# User_Interface.net
KiCad netlist of a schematic drawn in Altium Designer
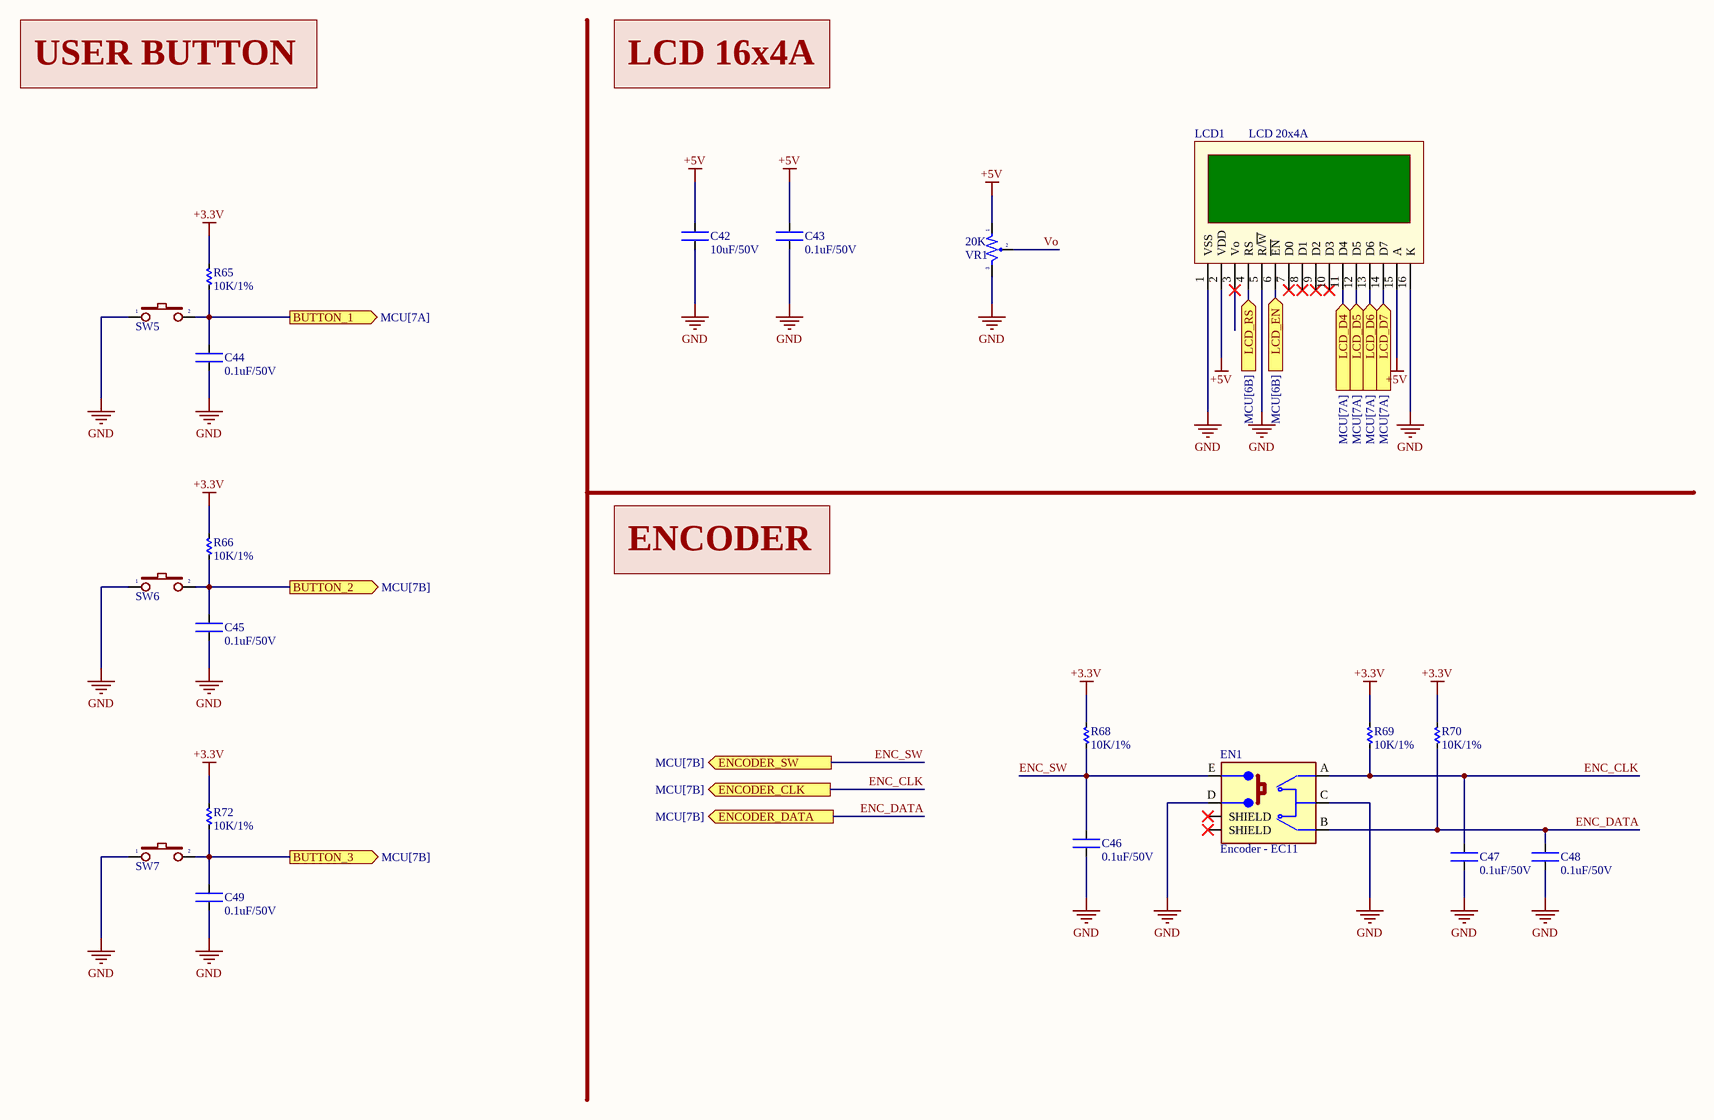
[diagram p0: User_Interface.SchDoc]

(export (version "E")
  (design (tool "Eeschema 10.0.6"))
  (components
    (comp (ref "C42")
      (value "10uF/50V")
      (footprint "CAP - 0603")
      (description "CAPACITOR SMD - KEMET")
      (libsource (lib "NewLibrary") (part "CAPACITOR"))
    )
    (comp (ref "C43")
      (value "0.1uF/50V")
      (footprint "CAP - 0603")
      (description "CAPACITOR SMD - KEMET")
      (libsource (lib "NewLibrary") (part "CAPACITOR"))
    )
    (comp (ref "C44")
      (value "0.1uF/50V")
      (footprint "CAP - 0603")
      (description "CAPACITOR SMD - KEMET")
      (libsource (lib "NewLibrary") (part "CAPACITOR"))
    )
    (comp (ref "C45")
      (value "0.1uF/50V")
      (footprint "CAP - 0603")
      (description "CAPACITOR SMD - KEMET")
      (libsource (lib "NewLibrary") (part "CAPACITOR"))
    )
    (comp (ref "C46")
      (value "0.1uF/50V")
      (footprint "CAP - 0603")
      (description "CAPACITOR SMD - KEMET")
      (libsource (lib "NewLibrary") (part "CAPACITOR"))
    )
    (comp (ref "C47")
      (value "0.1uF/50V")
      (footprint "CAP - 0603")
      (description "CAPACITOR SMD - KEMET")
      (libsource (lib "NewLibrary") (part "CAPACITOR"))
    )
    (comp (ref "C48")
      (value "0.1uF/50V")
      (footprint "CAP - 0603")
      (description "CAPACITOR SMD - KEMET")
      (libsource (lib "NewLibrary") (part "CAPACITOR"))
    )
    (comp (ref "C49")
      (value "0.1uF/50V")
      (footprint "CAP - 0603")
      (description "CAPACITOR SMD - KEMET")
      (libsource (lib "NewLibrary") (part "CAPACITOR"))
    )
    (comp (ref "EN1")
      (value "Encoder - EC11")
      (footprint "Encoder - EC11")
      (description "Bourns PEC11R-4015F-S0024")
      (libsource (lib "NewLibrary") (part "Encoder - EC11"))
    )
    (comp (ref "LCD1")
      (value "LCD 20x4A")
      (footprint "LCD-20x4A-4-Holes")
      (description "LCD 2004")
      (libsource (lib "NewLibrary") (part "LCD 20x4A"))
    )
    (comp (ref "R65")
      (value "10K/1%")
      (footprint "RES - 0603")
      (description "Resistor SMD - YAGEO")
      (libsource (lib "NewLibrary") (part "RESISTOR"))
    )
    (comp (ref "R66")
      (value "10K/1%")
      (footprint "RES - 0603")
      (description "Resistor SMD - YAGEO")
      (libsource (lib "NewLibrary") (part "RESISTOR"))
    )
    (comp (ref "R68")
      (value "10K/1%")
      (footprint "RES - 0603")
      (description "Resistor SMD - YAGEO")
      (libsource (lib "NewLibrary") (part "RESISTOR"))
    )
    (comp (ref "R69")
      (value "10K/1%")
      (footprint "RES - 0603")
      (description "Resistor SMD - YAGEO")
      (libsource (lib "NewLibrary") (part "RESISTOR"))
    )
    (comp (ref "R70")
      (value "10K/1%")
      (footprint "RES - 0603")
      (description "Resistor SMD - YAGEO")
      (libsource (lib "NewLibrary") (part "RESISTOR"))
    )
    (comp (ref "R72")
      (value "10K/1%")
      (footprint "RES - 0603")
      (description "Resistor SMD - YAGEO")
      (libsource (lib "NewLibrary") (part "RESISTOR"))
    )
    (comp (ref "SW5")
      (value "Button 4 Pins")
      (footprint "SW-SMD-6x6mm")
      (description "DIP Button 4 Pins")
      (libsource (lib "NewLibrary") (part "Button 4 Pins"))
    )
    (comp (ref "SW6")
      (value "Button 4 Pins")
      (footprint "SW-SMD-6x6mm")
      (description "DIP Button 4 Pins")
      (libsource (lib "NewLibrary") (part "Button 4 Pins"))
    )
    (comp (ref "SW7")
      (value "Button 4 Pins")
      (footprint "SW-SMD-6x6mm")
      (description "DIP Button 4 Pins")
      (libsource (lib "NewLibrary") (part "Button 4 Pins"))
    )
    (comp (ref "VR1")
      (value "20K")
      (footprint "VR 3x3")
      (description "VR")
      (libsource (lib "NewLibrary") (part "VARIABLE RESISTOR"))
    )
  )
  (nets
    (net (code "1") (name "+3.3V") (class "Default")
      (node (ref "R65") (pin "2") (pinfunction "2_2") (pintype "passive"))
      (node (ref "R66") (pin "2") (pinfunction "2_2") (pintype "passive"))
      (node (ref "R68") (pin "2") (pinfunction "2_2") (pintype "passive"))
      (node (ref "R69") (pin "2") (pinfunction "2_2") (pintype "passive"))
      (node (ref "R70") (pin "2") (pinfunction "2_2") (pintype "passive"))
      (node (ref "R72") (pin "1") (pinfunction "1_1") (pintype "passive"))
    )
    (net (code "2") (name "+5V") (class "Default")
      (node (ref "C42") (pin "2") (pinfunction "2_2") (pintype "passive"))
      (node (ref "C43") (pin "2") (pinfunction "2_2") (pintype "passive"))
      (node (ref "LCD1") (pin "15") (pinfunction "A_15") (pintype "passive"))
      (node (ref "LCD1") (pin "2") (pinfunction "VDD_2") (pintype "passive"))
      (node (ref "VR1") (pin "1") (pinfunction "1_1") (pintype "passive"))
    )
    (net (code "3") (name "/BUTTON_1") (class "Default")
      (node (ref "C44") (pin "2") (pinfunction "2_2") (pintype "passive"))
      (node (ref "R65") (pin "1") (pinfunction "1_1") (pintype "passive"))
      (node (ref "SW5") (pin "2") (pinfunction "2_2") (pintype "passive"))
    )
    (net (code "4") (name "/BUTTON_2") (class "Default")
      (node (ref "C45") (pin "2") (pinfunction "2_2") (pintype "passive"))
      (node (ref "R66") (pin "1") (pinfunction "1_1") (pintype "passive"))
      (node (ref "SW6") (pin "2") (pinfunction "2_2") (pintype "passive"))
    )
    (net (code "5") (name "/BUTTON_3") (class "Default")
      (node (ref "C49") (pin "2") (pinfunction "2_2") (pintype "passive"))
      (node (ref "R72") (pin "2") (pinfunction "2_2") (pintype "passive"))
      (node (ref "SW7") (pin "2") (pinfunction "2_2") (pintype "passive"))
    )
    (net (code "6") (name "/ENC_CLK") (class "Default")
      (node (ref "C47") (pin "2") (pinfunction "2_2") (pintype "passive"))
      (node (ref "EN1") (pin "A") (pinfunction "A_A") (pintype "passive"))
      (node (ref "R69") (pin "1") (pinfunction "1_1") (pintype "passive"))
    )
    (net (code "7") (name "/ENC_DATA") (class "Default")
      (node (ref "C48") (pin "2") (pinfunction "2_2") (pintype "passive"))
      (node (ref "EN1") (pin "B") (pinfunction "B_B") (pintype "passive"))
      (node (ref "R70") (pin "1") (pinfunction "1_1") (pintype "passive"))
    )
    (net (code "8") (name "/ENC_SW") (class "Default")
      (node (ref "C46") (pin "2") (pinfunction "2_2") (pintype "passive"))
      (node (ref "EN1") (pin "E") (pinfunction "S2_E") (pintype "passive"))
      (node (ref "R68") (pin "1") (pinfunction "1_1") (pintype "passive"))
    )
    (net (code "9") (name "/LCD_D4") (class "Default")
      (node (ref "LCD1") (pin "11") (pinfunction "D4_11") (pintype "passive"))
    )
    (net (code "10") (name "/LCD_D5") (class "Default")
      (node (ref "LCD1") (pin "12") (pinfunction "D5_12") (pintype "passive"))
    )
    (net (code "11") (name "/LCD_D6") (class "Default")
      (node (ref "LCD1") (pin "13") (pinfunction "D6_13") (pintype "passive"))
    )
    (net (code "12") (name "/LCD_D7") (class "Default")
      (node (ref "LCD1") (pin "14") (pinfunction "D7_14") (pintype "passive"))
    )
    (net (code "13") (name "/LCD_EN") (class "Default")
      (node (ref "LCD1") (pin "6") (pinfunction "~{EN}_6") (pintype "passive"))
    )
    (net (code "14") (name "/LCD_RS") (class "Default")
      (node (ref "LCD1") (pin "4") (pinfunction "RS_4") (pintype "passive"))
    )
    (net (code "15") (name "/Vo") (class "Default")
      (node (ref "VR1") (pin "2") (pinfunction "2_2") (pintype "passive"))
    )
    (net (code "16") (name "GND") (class "Default")
      (node (ref "C42") (pin "1") (pinfunction "1_1") (pintype "passive"))
      (node (ref "C43") (pin "1") (pinfunction "1_1") (pintype "passive"))
      (node (ref "C44") (pin "1") (pinfunction "1_1") (pintype "passive"))
      (node (ref "C45") (pin "1") (pinfunction "1_1") (pintype "passive"))
      (node (ref "C46") (pin "1") (pinfunction "1_1") (pintype "passive"))
      (node (ref "C47") (pin "1") (pinfunction "1_1") (pintype "passive"))
      (node (ref "C48") (pin "1") (pinfunction "1_1") (pintype "passive"))
      (node (ref "C49") (pin "1") (pinfunction "1_1") (pintype "passive"))
      (node (ref "EN1") (pin "C") (pinfunction "C_C") (pintype "passive"))
      (node (ref "EN1") (pin "D") (pinfunction "S1_D") (pintype "passive"))
      (node (ref "LCD1") (pin "1") (pinfunction "VSS_1") (pintype "passive"))
      (node (ref "LCD1") (pin "16") (pinfunction "K_16") (pintype "passive"))
      (node (ref "LCD1") (pin "5") (pinfunction "R/~{W}_5") (pintype "passive"))
      (node (ref "SW5") (pin "1") (pinfunction "1_1") (pintype "passive"))
      (node (ref "SW6") (pin "1") (pinfunction "1_1") (pintype "passive"))
      (node (ref "SW7") (pin "1") (pinfunction "1_1") (pintype "passive"))
      (node (ref "VR1") (pin "3") (pinfunction "3_3") (pintype "passive"))
    )
    (net (code "17") (name "unconnected-(EN1-SHIELD-PadSH1)") (class "Default")
      (node (ref "EN1") (pin "SH1") (pinfunction "SHIELD_SH1") (pintype "passive+no_connect"))
    )
    (net (code "18") (name "unconnected-(EN1-SHIELD-PadSH2)") (class "Default")
      (node (ref "EN1") (pin "SH2") (pinfunction "SHIELD_SH2") (pintype "passive+no_connect"))
    )
    (net (code "19") (name "unconnected-(LCD1-D0-Pad7)") (class "Default")
      (node (ref "LCD1") (pin "7") (pinfunction "D0_7") (pintype "passive+no_connect"))
    )
    (net (code "20") (name "unconnected-(LCD1-D1-Pad8)") (class "Default")
      (node (ref "LCD1") (pin "8") (pinfunction "D1_8") (pintype "passive+no_connect"))
    )
    (net (code "21") (name "unconnected-(LCD1-D2-Pad9)") (class "Default")
      (node (ref "LCD1") (pin "9") (pinfunction "D2_9") (pintype "passive+no_connect"))
    )
    (net (code "22") (name "unconnected-(LCD1-D3-Pad10)") (class "Default")
      (node (ref "LCD1") (pin "10") (pinfunction "D3_10") (pintype "passive+no_connect"))
    )
    (net (code "23") (name "unconnected-(LCD1-Vo-Pad3)") (class "Default")
      (node (ref "LCD1") (pin "3") (pinfunction "Vo_3") (pintype "passive+no_connect"))
    )
  )
)
